# Sheet1.net
KiCad netlist of a schematic drawn in Altium Designer
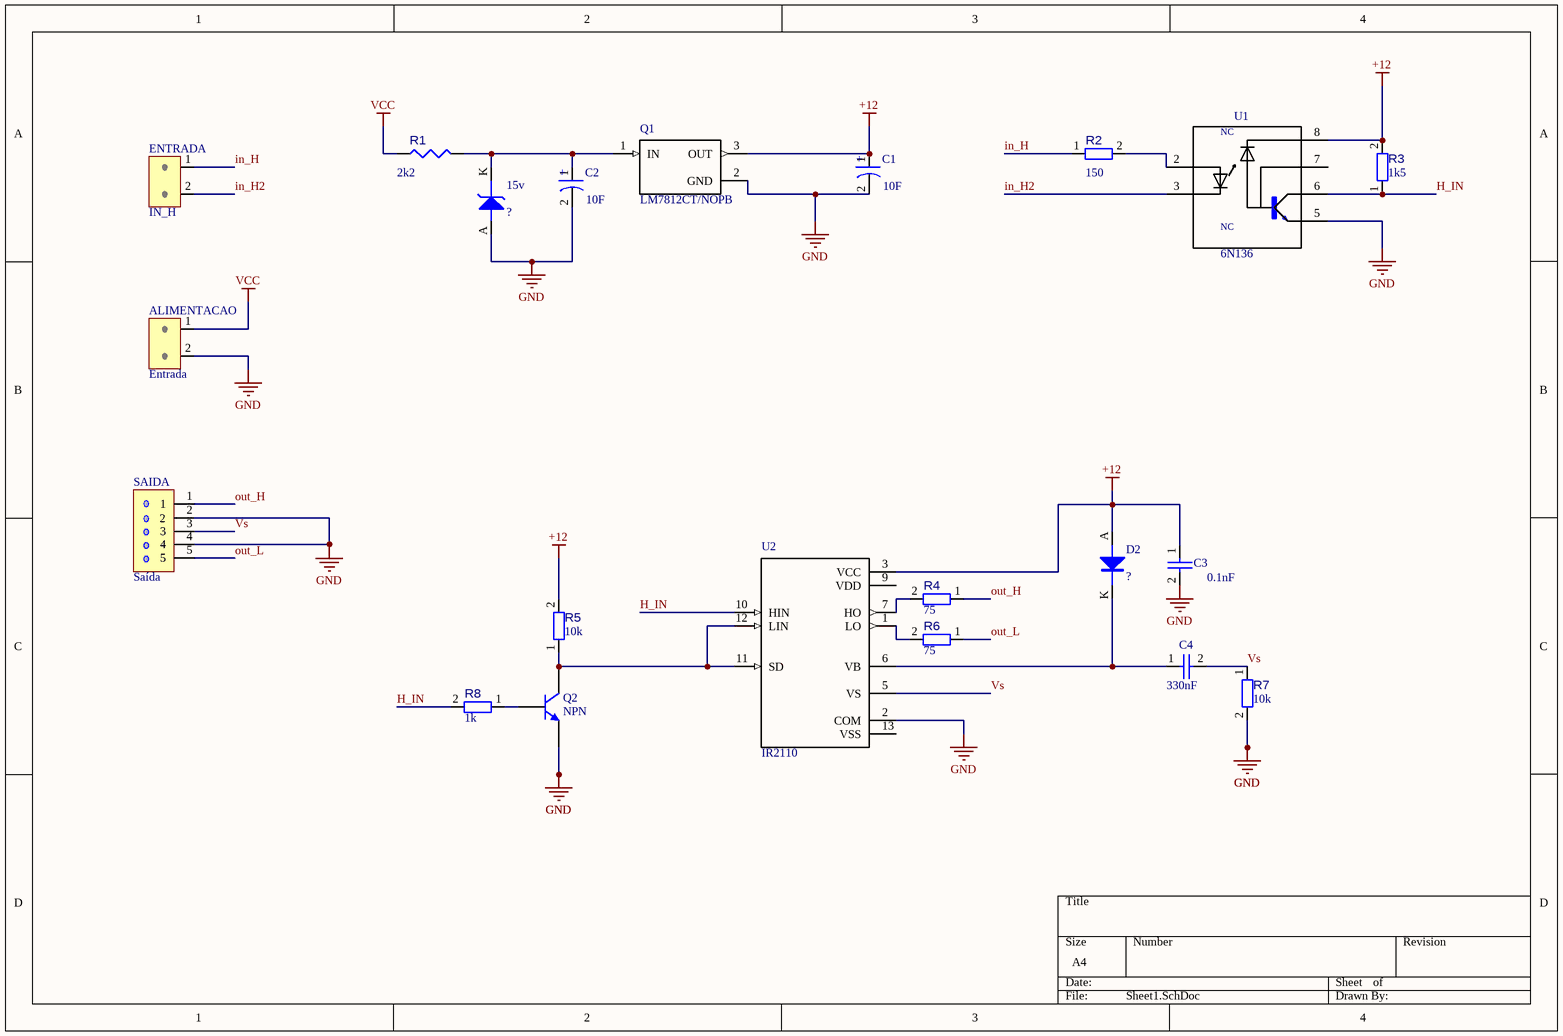
[diagram p0: Sheet1.SchDoc]

(export (version "E")
  (design (tool "Eeschema 10.0.6"))
  (components
    (comp (ref "15v")
      (value "?")
      (footprint "DIO_PTH_DO35")
      (fields (field (name "Comment") "DIO_ZENER_DO35"))
      (libsource (lib "i9Library_Altium") (part "DIO_ZENER_DO35"))
    )
    (comp (ref "ALIMENTACAO")
      (value "Entrada")
      (footprint "HEADER_1X2")
      (description "MKDS_2")
      (libsource (lib "i9Library_Altium") (part "CN_MKDS_2"))
    )
    (comp (ref "C1")
      (value "10F")
      (footprint "CAP_ALU_RADIAL_5MM")
      (description "PTH Radial Electrolytic Capacitor")
      (fields (field (name "Comment") "Electrolytic Capacitor"))
      (libsource (lib "i9Library_Altium") (part "CAP_ALU_RADIAL_5MM"))
    )
    (comp (ref "C2")
      (value "10F")
      (footprint "CAP_ALU_RADIAL_5MM")
      (description "PTH Radial Electrolytic Capacitor")
      (fields (field (name "Comment") "Electrolytic Capacitor"))
      (libsource (lib "i9Library_Altium") (part "CAP_ALU_RADIAL_5MM"))
    )
    (comp (ref "C3")
      (value "0.1nF")
      (footprint "Cap_POL_RADIAL_10mm")
      (description "PTH Radial Polyester Capacitor")
      (fields (field (name "Comment") "CAP_POL_RADIAL_16MM"))
      (libsource (lib "i9Library_Altium") (part "CAP_POL_RADIAL_16MM"))
    )
    (comp (ref "C4")
      (value "330nF")
      (footprint "CAP_POL_RADIAL_16MM")
      (description "PTH Radial Polyester Capacitor")
      (fields (field (name "Comment") "CAP_POL_RADIAL_25.5MM"))
      (libsource (lib "i9Library_Altium") (part "CAP_POL_RADIAL_25.5MM"))
    )
    (comp (ref "D2")
      (value "?")
      (footprint "DIO_PTH_DO41")
      (fields (field (name "Comment") "DIO_PTH_1N4007"))
      (libsource (lib "i9Library_Altium") (part "DIO_PTH_1N4007"))
    )
    (comp (ref "ENTRADA")
      (value "IN_H")
      (footprint "HEADER_1X2")
      (description "MKDS_2")
      (libsource (lib "i9Library_Altium") (part "CN_MKDS_2"))
    )
    (comp (ref "Q1")
      (value "LM7812CT/NOPB")
      (footprint "*TO254P1054X470X2600-3")
      (description "Linear Voltage Regulator IC Positive Fixed 1 Output 1A TO-220-3")
      (fields (field (name "MP") "LM7805CT") (field (name "MF") "ON Semiconductor"))
      (libsource (lib "LM7805CT_NOPB") (part "LM7805CT/NOPB"))
    )
    (comp (ref "Q2")
      (value "NPN")
      (footprint "369-03")
      (description "NPN Bipolar Transistor")
      (fields (field (name "PUBLISHER") "Altium Limited"))
      (libsource (lib "Miscellaneous Devices") (part "NPN"))
    )
    (comp (ref "R1")
      (value "2k2")
      (footprint "RES_PTH_7.62MM")
      (description "Pin Through Hole Resistor 7.62mm")
      (libsource (lib "i9Library_Altium") (part "RES_PTH_7.62MM"))
    )
    (comp (ref "R2")
      (value "150")
      (footprint "RES_PTH_7.62MM")
      (description "SMD 0805 Resistor")
      (libsource (lib "") (part "RES_SMD_0805_2"))
    )
    (comp (ref "R3")
      (value "1k5")
      (footprint "RES_PTH_7.62MM")
      (description "SMD 0805 Resistor")
      (libsource (lib "i9Library_Altium") (part "RES_SMD_0805"))
    )
    (comp (ref "R4")
      (value "75")
      (footprint "RES_PTH_7.62MM")
      (description "SMD 0805 Resistor")
      (libsource (lib "") (part "RES_SMD_0805_1"))
    )
    (comp (ref "R5")
      (value "10k")
      (footprint "RES_PTH_7.62MM")
      (description "SMD 0805 Resistor")
      (libsource (lib "i9Library_Altium") (part "RES_SMD_0805"))
    )
    (comp (ref "R6")
      (value "75")
      (footprint "RES_PTH_7.62MM")
      (description "SMD 0805 Resistor")
      (libsource (lib "") (part "RES_SMD_0805_1"))
    )
    (comp (ref "R7")
      (value "10k")
      (footprint "RES_PTH_7.62MM")
      (description "SMD 0805 Resistor")
      (libsource (lib "") (part "RES_SMD_0805_3"))
    )
    (comp (ref "R8")
      (value "1k")
      (footprint "RES_PTH_7.62MM")
      (description "SMD 0805 Resistor")
      (libsource (lib "") (part "RES_SMD_0805_1"))
    )
    (comp (ref "SAIDA")
      (value "Saída")
      (footprint "CN_KK_5_5045-5")
      (description "KK_5")
      (libsource (lib "i9Library_Altium") (part "CN_KK_5"))
    )
    (comp (ref "U1")
      (value "6N136")
      (footprint "*DIP762W50P254L977H451Q8")
      (description "Optocoupler DC-IN 1-CH Transistor With Base DC-OUT 8-Pin PDIP")
      (fields (field (name "MF") "Vishay Semiconductor"))
      (libsource (lib "6N136") (part "6N136"))
    )
    (comp (ref "U2")
      (value "IR2110")
      (footprint "*DIP762W45P254L2019H533Q14")
      (description "Half-Bridge Gate Driver IC Non-Inverting 14-DIP")
      (fields (field (name "MF") "Infineon"))
      (libsource (lib "IR2110") (part "IR2110"))
    )
  )
  (nets
    (net (code "1") (name "+12") (class "Default")
      (node (ref "C1") (pin "1") (pinfunction "1_1") (pintype "passive"))
      (node (ref "C3") (pin "1") (pintype "passive"))
      (node (ref "D2") (pin "A") (pintype "passive"))
      (node (ref "Q1") (pin "3") (pinfunction "OUT_3") (pintype "output"))
      (node (ref "R3") (pin "2") (pinfunction "2_2") (pintype "passive"))
      (node (ref "R5") (pin "2") (pinfunction "2_2") (pintype "passive"))
      (node (ref "U1") (pin "8") (pinfunction "C/VCC_8") (pintype "passive"))
      (node (ref "U2") (pin "3") (pinfunction "VCC_3") (pintype "power_in"))
    )
    (net (code "2") (name "/H_IN") (class "Default")
      (node (ref "R3") (pin "1") (pinfunction "1_1") (pintype "passive"))
      (node (ref "R8") (pin "2") (pinfunction "2_2") (pintype "passive"))
      (node (ref "U1") (pin "6") (pinfunction "C/VO_6") (pintype "passive"))
      (node (ref "U2") (pin "10") (pinfunction "HIN_10") (pintype "input"))
    )
    (net (code "3") (name "/Vs") (class "Default")
      (node (ref "C4") (pin "2") (pintype "passive"))
      (node (ref "R7") (pin "1") (pinfunction "1_1") (pintype "passive"))
      (node (ref "SAIDA") (pin "3") (pinfunction "3_3") (pintype "passive"))
      (node (ref "U2") (pin "5") (pinfunction "VS_5") (pintype "passive"))
    )
    (net (code "4") (name "/in_H") (class "Default")
      (node (ref "ENTRADA") (pin "1") (pintype "passive"))
      (node (ref "R2") (pin "1") (pinfunction "1_1") (pintype "passive"))
    )
    (net (code "5") (name "/in_H2") (class "Default")
      (node (ref "ENTRADA") (pin "2") (pinfunction "2_2") (pintype "passive"))
      (node (ref "U1") (pin "3") (pinfunction "C_3") (pintype "passive"))
    )
    (net (code "6") (name "/out_H") (class "Default")
      (node (ref "R4") (pin "1") (pinfunction "1_1") (pintype "passive"))
      (node (ref "SAIDA") (pin "1") (pinfunction "1_1") (pintype "passive"))
    )
    (net (code "7") (name "/out_L") (class "Default")
      (node (ref "R6") (pin "1") (pinfunction "1_1") (pintype "passive"))
      (node (ref "SAIDA") (pin "5") (pinfunction "5_5") (pintype "passive"))
    )
    (net (code "8") (name "GND") (class "Default")
      (node (ref "15v") (pin "A") (pintype "passive"))
      (node (ref "ALIMENTACAO") (pin "2") (pinfunction "2_2") (pintype "passive"))
      (node (ref "C1") (pin "2") (pintype "passive"))
      (node (ref "C2") (pin "2") (pintype "passive"))
      (node (ref "C3") (pin "2") (pintype "passive"))
      (node (ref "Q1") (pin "2") (pinfunction "GND_2") (pintype "power_in"))
      (node (ref "Q2") (pin "3") (pinfunction "E_3") (pintype "passive"))
      (node (ref "R7") (pin "2") (pinfunction "2_2") (pintype "passive"))
      (node (ref "SAIDA") (pin "2") (pinfunction "2_2") (pintype "passive"))
      (node (ref "SAIDA") (pin "4") (pinfunction "4_4") (pintype "passive"))
      (node (ref "U1") (pin "5") (pinfunction "E/GND_5") (pintype "passive"))
      (node (ref "U2") (pin "2") (pinfunction "COM_2") (pintype "power_in"))
    )
    (net (code "9") (name "Net-(Q1-IN)") (class "Default")
      (node (ref "15v") (pin "K") (pintype "passive"))
      (node (ref "C2") (pin "1") (pinfunction "1_1") (pintype "passive"))
      (node (ref "Q1") (pin "1") (pinfunction "IN_1") (pintype "input"))
      (node (ref "R1") (pin "2") (pinfunction "2_2") (pintype "passive"))
    )
    (net (code "10") (name "Net-(Q2-B)") (class "Default")
      (node (ref "Q2") (pin "2") (pinfunction "B_2") (pintype "passive"))
      (node (ref "R8") (pin "1") (pinfunction "1_1") (pintype "passive"))
    )
    (net (code "11") (name "Net-(Q2-C)") (class "Default")
      (node (ref "Q2") (pin "1") (pinfunction "C_1") (pintype "passive"))
      (node (ref "R5") (pin "1") (pinfunction "1_1") (pintype "passive"))
      (node (ref "U2") (pin "11") (pinfunction "SD_11") (pintype "input"))
      (node (ref "U2") (pin "12") (pinfunction "LIN_12") (pintype "input"))
    )
    (net (code "12") (name "Net-(U1-A)") (class "Default")
      (node (ref "R2") (pin "2") (pinfunction "2_2") (pintype "passive"))
      (node (ref "U1") (pin "2") (pinfunction "A_2") (pintype "passive"))
    )
    (net (code "13") (name "Net-(U2-HO)") (class "Default")
      (node (ref "R4") (pin "2") (pinfunction "2_2") (pintype "passive"))
      (node (ref "U2") (pin "7") (pinfunction "HO_7") (pintype "output"))
    )
    (net (code "14") (name "Net-(U2-LO)") (class "Default")
      (node (ref "R6") (pin "2") (pinfunction "2_2") (pintype "passive"))
      (node (ref "U2") (pin "1") (pinfunction "LO_1") (pintype "output"))
    )
    (net (code "15") (name "Net-(U2-VB)") (class "Default")
      (node (ref "C4") (pin "1") (pintype "passive"))
      (node (ref "D2") (pin "K") (pintype "passive"))
      (node (ref "U2") (pin "6") (pinfunction "VB_6") (pintype "passive"))
    )
    (net (code "16") (name "VCC") (class "Default")
      (node (ref "ALIMENTACAO") (pin "1") (pintype "passive"))
      (node (ref "R1") (pin "1") (pinfunction "1_1") (pintype "passive"))
    )
    (net (code "17") (name "unconnected-(U1-B{slash}VB-Pad7)") (class "Default")
      (node (ref "U1") (pin "7") (pinfunction "B/VB_7") (pintype "passive"))
    )
    (net (code "18") (name "unconnected-(U2-VDD-Pad9)") (class "Default")
      (node (ref "U2") (pin "9") (pinfunction "VDD_9") (pintype "power_in"))
    )
    (net (code "19") (name "unconnected-(U2-VSS-Pad13)") (class "Default")
      (node (ref "U2") (pin "13") (pinfunction "VSS_13") (pintype "power_in"))
    )
  )
)
